# Sheet_1_2026-02-24.net
KiCad netlist of a schematic drawn in Altium Designer
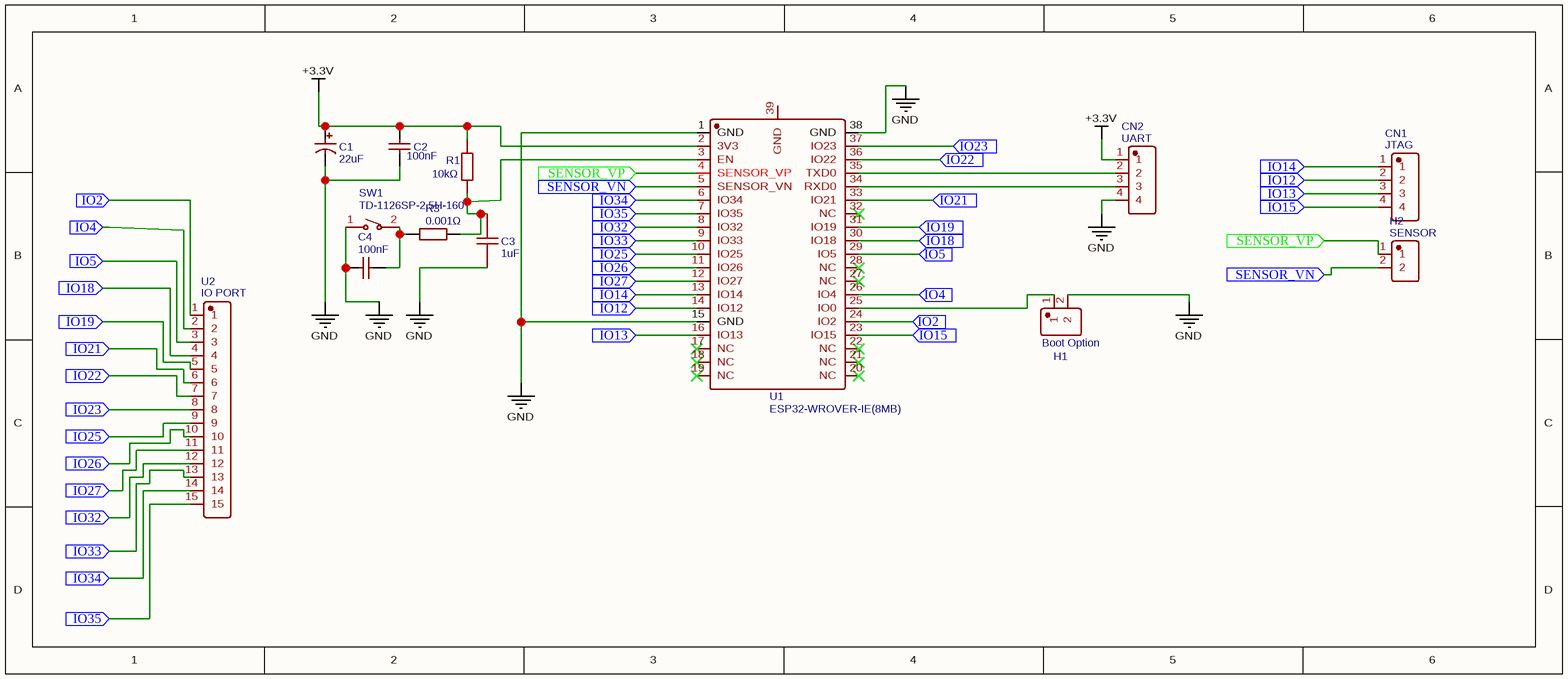
[diagram p0: Sheet_1_2026-02-24.schdoc]

(export (version "E")
  (design (tool "Eeschema 10.0.6"))
  (components
    (comp (ref "C1")
      (value "22uF")
      (fields
        (field (name "MANUFACTURER") "Samwha Capacitor")
        (field (name "MANUFACTURER PART") "RD1H226M05011PC18P")
        (field (name "CONTRIBUTOR") "LCSC")
      )
      (libsource (lib "altium-import") (part "root_3_22uF_"))
    )
    (comp (ref "C2")
      (value "100nF")
      (fields
        (field (name "MANUFACTURER") "FH")
        (field (name "MANUFACTURER PART") "CT42-104K17B500P")
        (field (name "CONTRIBUTOR") "LCSC")
      )
      (libsource (lib "altium-import") (part "root_3_100nF_"))
    )
    (comp (ref "C3")
      (value "1uF")
      (fields
        (field (name "MANUFACTURER") "Samwha Capacitor")
        (field (name "MANUFACTURER PART") "CS2012X7R105K500NRE")
        (field (name "CONTRIBUTOR") "LCSC")
      )
      (libsource (lib "altium-import") (part "root_3_1uF_"))
    )
    (comp (ref "C4")
      (value "100nF")
      (fields
        (field (name "MANUFACTURER") "FH")
        (field (name "MANUFACTURER PART") "CT42-104K17B500P")
        (field (name "CONTRIBUTOR") "LCSC")
      )
      (libsource (lib "altium-import") (part "root_2_100nF_"))
    )
    (comp (ref "CN1")
      (value "JTAG")
      (fields (field (name "CONTRIBUTOR") "LCSC"))
      (libsource (lib "altium-import") (part "root_0_JTAG_"))
    )
    (comp (ref "CN2")
      (value "UART")
      (fields (field (name "MANUFACTURER PART") "JTAG") (field (name "CONTRIBUTOR") "LCSC"))
      (libsource (lib "altium-import") (part "root_0_UART_"))
    )
    (comp (ref "H1")
      (value "Boot Option")
      (fields
        (field (name "MANUFACTURER") "CJT(长江连接器)")
        (field (name "MANUFACTURER PART") "A2541WV-2P")
        (field (name "CONTRIBUTOR") "lcsc")
      )
      (libsource (lib "altium-import") (part "root_1_Boot Option_"))
    )
    (comp (ref "H2")
      (value "SENSOR")
      (fields
        (field (name "MANUFACTURER") "CJT(长江连接器)")
        (field (name "MANUFACTURER PART") "A2541WV-2P")
        (field (name "CONTRIBUTOR") "lcsc")
      )
      (libsource (lib "altium-import") (part "root_0_SENSOR_"))
    )
    (comp (ref "R1")
      (value "10kΩ")
      (fields
        (field (name "MANUFACTURER") "ResistorToday")
        (field (name "MANUFACTURER PART") "PTFR0805B10K0N9")
        (field (name "CONTRIBUTOR") "LCSC")
      )
      (libsource (lib "altium-import") (part "root_3_10kΩ_"))
    )
    (comp (ref "R3")
      (value "0.001Ω")
      (fields
        (field (name "MANUFACTURER") "ResistorToday")
        (field (name "MANUFACTURER PART") "ECSR2512FR001K9")
        (field (name "CONTRIBUTOR") "LCSC")
      )
      (libsource (lib "altium-import") (part "root_0_0.001Ω_"))
    )
    (comp (ref "SW1")
      (value "TD-1126SP-2.5H-160")
      (fields (field (name "MANUFACTURER") "DEALON(德艺隆)") (field (name "CONTRIBUTOR") "LCSC"))
      (libsource (lib "altium-import") (part "root_0_TD-1126SP-2.5H-160_"))
    )
    (comp (ref "U1")
      (value "ESP32-WROVER-IE(8MB)")
      (fields (field (name "MANUFACTURER") "Espressif Systems") (field (name "CONTRIBUTOR") "LCSC"))
      (libsource (lib "altium-import") (part "root_0_ESP32-WROVER-IE(8MB)_"))
    )
    (comp (ref "U2")
      (value "IO PORT")
      (fields
        (field (name "MANUFACTURER") "XKB Connectivity(中国星坤)")
        (field (name "MANUFACTURER PART") "X1311WR-15J-C26D40")
        (field (name "CONTRIBUTOR") "LCSC")
      )
      (libsource (lib "altium-import") (part "root_0_IO PORT_"))
    )
  )
  (nets
    (net (code "1") (name "+3.3V") (class "Default")
      (node (ref "C1") (pin "1") (pinfunction "1_1") (pintype "passive"))
      (node (ref "C2") (pin "1") (pinfunction "1_1") (pintype "passive"))
      (node (ref "CN2") (pin "1") (pinfunction "1_1") (pintype "passive"))
      (node (ref "R1") (pin "1") (pinfunction "1_1") (pintype "passive"))
      (node (ref "U1") (pin "2") (pinfunction "3V3_2") (pintype "passive"))
    )
    (net (code "2") (name "/IO2") (class "Default")
      (node (ref "U1") (pin "24") (pinfunction "IO2_24") (pintype "passive"))
      (node (ref "U2") (pin "1") (pinfunction "1_1") (pintype "passive"))
    )
    (net (code "3") (name "/IO4") (class "Default")
      (node (ref "U1") (pin "26") (pinfunction "IO4_26") (pintype "passive"))
      (node (ref "U2") (pin "2") (pinfunction "2_2") (pintype "passive"))
    )
    (net (code "4") (name "/IO5") (class "Default")
      (node (ref "U1") (pin "29") (pinfunction "IO5_29") (pintype "passive"))
      (node (ref "U2") (pin "3") (pinfunction "3_3") (pintype "passive"))
    )
    (net (code "5") (name "/IO12") (class "Default")
      (node (ref "CN1") (pin "2") (pinfunction "2_2") (pintype "passive"))
      (node (ref "U1") (pin "14") (pinfunction "IO12_14") (pintype "passive"))
    )
    (net (code "6") (name "/IO13") (class "Default")
      (node (ref "CN1") (pin "3") (pinfunction "3_3") (pintype "passive"))
      (node (ref "U1") (pin "16") (pinfunction "IO13_16") (pintype "passive"))
    )
    (net (code "7") (name "/IO14") (class "Default")
      (node (ref "CN1") (pin "1") (pinfunction "1_1") (pintype "passive"))
      (node (ref "U1") (pin "13") (pinfunction "IO14_13") (pintype "passive"))
    )
    (net (code "8") (name "/IO15") (class "Default")
      (node (ref "CN1") (pin "4") (pinfunction "4_4") (pintype "passive"))
      (node (ref "U1") (pin "23") (pinfunction "IO15_23") (pintype "passive"))
    )
    (net (code "9") (name "/IO18") (class "Default")
      (node (ref "U1") (pin "30") (pinfunction "IO18_30") (pintype "passive"))
      (node (ref "U2") (pin "4") (pinfunction "4_4") (pintype "passive"))
    )
    (net (code "10") (name "/IO19") (class "Default")
      (node (ref "U1") (pin "31") (pinfunction "IO19_31") (pintype "passive"))
      (node (ref "U2") (pin "5") (pinfunction "5_5") (pintype "passive"))
    )
    (net (code "11") (name "/IO21") (class "Default")
      (node (ref "U1") (pin "33") (pinfunction "IO21_33") (pintype "passive"))
      (node (ref "U2") (pin "6") (pinfunction "6_6") (pintype "passive"))
    )
    (net (code "12") (name "/IO22") (class "Default")
      (node (ref "U1") (pin "36") (pinfunction "IO22_36") (pintype "passive"))
      (node (ref "U2") (pin "7") (pinfunction "7_7") (pintype "passive"))
    )
    (net (code "13") (name "/IO23") (class "Default")
      (node (ref "U1") (pin "37") (pinfunction "IO23_37") (pintype "passive"))
      (node (ref "U2") (pin "8") (pinfunction "8_8") (pintype "passive"))
    )
    (net (code "14") (name "/IO25") (class "Default")
      (node (ref "U1") (pin "10") (pinfunction "IO25_10") (pintype "passive"))
      (node (ref "U2") (pin "9") (pinfunction "9_9") (pintype "passive"))
    )
    (net (code "15") (name "/IO26") (class "Default")
      (node (ref "U1") (pin "11") (pinfunction "IO26_11") (pintype "passive"))
      (node (ref "U2") (pin "10") (pinfunction "10_10") (pintype "passive"))
    )
    (net (code "16") (name "/IO27") (class "Default")
      (node (ref "U1") (pin "12") (pinfunction "IO27_12") (pintype "passive"))
      (node (ref "U2") (pin "11") (pinfunction "11_11") (pintype "passive"))
    )
    (net (code "17") (name "/IO32") (class "Default")
      (node (ref "U1") (pin "8") (pinfunction "IO32_8") (pintype "passive"))
      (node (ref "U2") (pin "12") (pinfunction "12_12") (pintype "passive"))
    )
    (net (code "18") (name "/IO33") (class "Default")
      (node (ref "U1") (pin "9") (pinfunction "IO33_9") (pintype "passive"))
      (node (ref "U2") (pin "13") (pinfunction "13_13") (pintype "passive"))
    )
    (net (code "19") (name "/IO34") (class "Default")
      (node (ref "U1") (pin "6") (pinfunction "IO34_6") (pintype "passive"))
      (node (ref "U2") (pin "14") (pinfunction "14_14") (pintype "passive"))
    )
    (net (code "20") (name "/IO35") (class "Default")
      (node (ref "U1") (pin "7") (pinfunction "IO35_7") (pintype "passive"))
      (node (ref "U2") (pin "15") (pinfunction "15_15") (pintype "passive"))
    )
    (net (code "21") (name "/SENSOR_VN") (class "Default")
      (node (ref "H2") (pin "2") (pinfunction "2_2") (pintype "passive"))
      (node (ref "U1") (pin "5") (pinfunction "SENSOR_VN_5") (pintype "passive"))
    )
    (net (code "22") (name "/SENSOR_VP") (class "Default")
      (node (ref "H2") (pin "1") (pinfunction "1_1") (pintype "passive"))
      (node (ref "U1") (pin "4") (pinfunction "SENSOR_VP_4") (pintype "passive"))
    )
    (net (code "23") (name "GND") (class "Default")
      (node (ref "C1") (pin "2") (pinfunction "2_2") (pintype "passive"))
      (node (ref "C2") (pin "2") (pinfunction "2_2") (pintype "passive"))
      (node (ref "C3") (pin "2") (pinfunction "2_2") (pintype "passive"))
      (node (ref "C4") (pin "2") (pinfunction "2_2") (pintype "passive"))
      (node (ref "CN2") (pin "4") (pinfunction "4_4") (pintype "passive"))
      (node (ref "H1") (pin "2") (pinfunction "2_2") (pintype "passive"))
      (node (ref "SW1") (pin "1") (pinfunction "1_1") (pintype "passive"))
      (node (ref "U1") (pin "1") (pinfunction "GND_1") (pintype "passive"))
      (node (ref "U1") (pin "15") (pinfunction "GND_15") (pintype "passive"))
      (node (ref "U1") (pin "38") (pinfunction "GND_38") (pintype "passive"))
    )
    (net (code "24") (name "Net-(C4-Pad1)") (class "Default")
      (node (ref "C4") (pin "1") (pinfunction "1_1") (pintype "passive"))
      (node (ref "R3") (pin "1") (pinfunction "1_1") (pintype "passive"))
      (node (ref "SW1") (pin "2") (pinfunction "2_2") (pintype "passive"))
    )
    (net (code "25") (name "Net-(U1-EN)") (class "Default")
      (node (ref "C3") (pin "1") (pinfunction "1_1") (pintype "passive"))
      (node (ref "R1") (pin "2") (pinfunction "2_2") (pintype "passive"))
      (node (ref "R3") (pin "2") (pinfunction "2_2") (pintype "passive"))
      (node (ref "U1") (pin "3") (pinfunction "EN_3") (pintype "passive"))
    )
    (net (code "26") (name "Net-(U1-IO0)") (class "Default")
      (node (ref "H1") (pin "1") (pinfunction "1_1") (pintype "passive"))
      (node (ref "U1") (pin "25") (pinfunction "IO0_25") (pintype "passive"))
    )
    (net (code "27") (name "Net-(U1-RXD0)") (class "Default")
      (node (ref "CN2") (pin "3") (pinfunction "3_3") (pintype "passive"))
      (node (ref "U1") (pin "34") (pinfunction "RXD0_34") (pintype "passive"))
    )
    (net (code "28") (name "Net-(U1-TXD0)") (class "Default")
      (node (ref "CN2") (pin "2") (pinfunction "2_2") (pintype "passive"))
      (node (ref "U1") (pin "35") (pinfunction "TXD0_35") (pintype "passive"))
    )
    (net (code "29") (name "unconnected-(U1-GND-Pad39)") (class "Default")
      (node (ref "U1") (pin "39") (pinfunction "GND_39") (pintype "passive"))
    )
    (net (code "30") (name "unconnected-(U1-NC-Pad17)") (class "Default")
      (node (ref "U1") (pin "17") (pinfunction "NC_17") (pintype "passive+no_connect"))
    )
    (net (code "31") (name "unconnected-(U1-NC-Pad18)") (class "Default")
      (node (ref "U1") (pin "18") (pinfunction "NC_18") (pintype "passive+no_connect"))
    )
    (net (code "32") (name "unconnected-(U1-NC-Pad19)") (class "Default")
      (node (ref "U1") (pin "19") (pinfunction "NC_19") (pintype "passive+no_connect"))
    )
    (net (code "33") (name "unconnected-(U1-NC-Pad20)") (class "Default")
      (node (ref "U1") (pin "20") (pinfunction "NC_20") (pintype "passive+no_connect"))
    )
    (net (code "34") (name "unconnected-(U1-NC-Pad21)") (class "Default")
      (node (ref "U1") (pin "21") (pinfunction "NC_21") (pintype "passive+no_connect"))
    )
    (net (code "35") (name "unconnected-(U1-NC-Pad22)") (class "Default")
      (node (ref "U1") (pin "22") (pinfunction "NC_22") (pintype "passive+no_connect"))
    )
    (net (code "36") (name "unconnected-(U1-NC-Pad27)") (class "Default")
      (node (ref "U1") (pin "27") (pinfunction "NC_27") (pintype "passive+no_connect"))
    )
    (net (code "37") (name "unconnected-(U1-NC-Pad28)") (class "Default")
      (node (ref "U1") (pin "28") (pinfunction "NC_28") (pintype "passive+no_connect"))
    )
    (net (code "38") (name "unconnected-(U1-NC-Pad32)") (class "Default")
      (node (ref "U1") (pin "32") (pinfunction "NC_32") (pintype "passive+no_connect"))
    )
  )
)
